# iotv2.net
KiCad netlist of a schematic drawn in Altium Designer
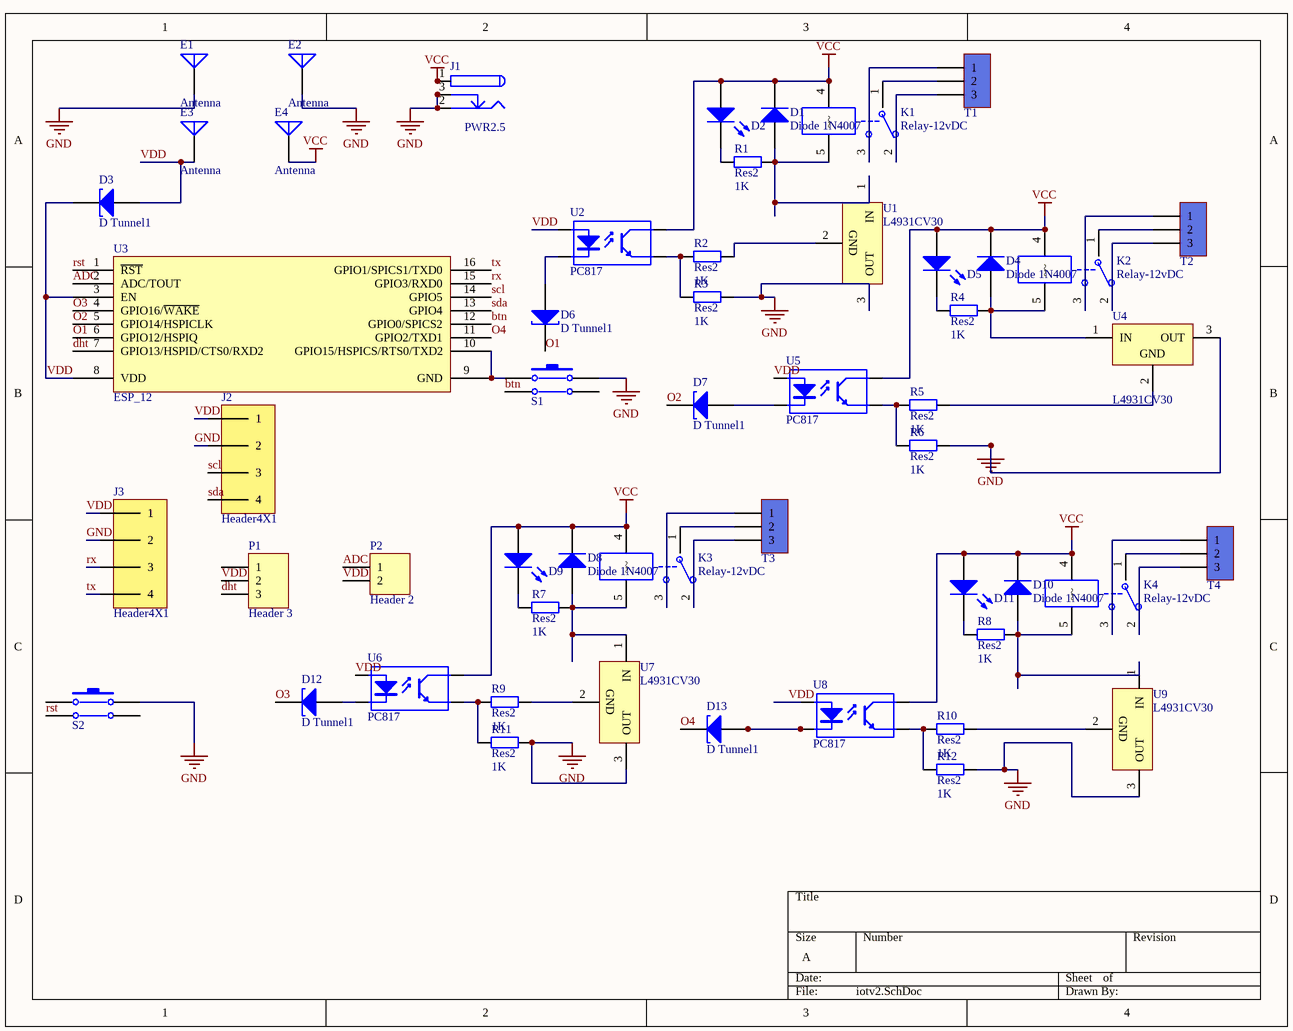
[diagram p0: iotv2.SchDoc]

(export (version "E")
  (design (tool "Eeschema 10.0.6"))
  (components
    (comp (ref "D1")
      (value "Diode 1N4007")
      (footprint "DO-41")
      (description "1 Amp General Purpose Rectifier")
      (fields (field (name "PUBLISHER") "Altium Limited"))
      (libsource (lib "Miscellaneous Devices") (part "Diode 1N4007"))
    )
    (comp (ref "D2")
      (value "LED 3mm")
      (footprint "LED-3mm")
      (description "Typical LED")
      (fields (field (name "DESIGNER") "Seyed Mohsen Ghasemian") (field (name "PUBLISHER") "www.picpars.com"))
      (libsource (lib "PicPars.com_usefully_Library") (part "LED 3mm"))
    )
    (comp (ref "D3")
      (value "D Tunnel1")
      (footprint "3.2X1.6X1.1")
      (description "Tunnel Diode - RLC Model")
      (fields (field (name "PUBLISHER") "Altium Limited"))
      (libsource (lib "Miscellaneous Devices") (part "D Tunnel1"))
    )
    (comp (ref "D4")
      (value "Diode 1N4007")
      (footprint "DO-41")
      (description "1 Amp General Purpose Rectifier")
      (fields (field (name "PUBLISHER") "Altium Limited"))
      (libsource (lib "Miscellaneous Devices") (part "Diode 1N4007"))
    )
    (comp (ref "D5")
      (value "LED 3mm")
      (footprint "LED-3mm")
      (description "Typical LED")
      (fields (field (name "DESIGNER") "Seyed Mohsen Ghasemian") (field (name "PUBLISHER") "www.picpars.com"))
      (libsource (lib "PicPars.com_usefully_Library") (part "LED 3mm"))
    )
    (comp (ref "D6")
      (value "D Tunnel1")
      (footprint "3.2X1.6X1.1")
      (description "Tunnel Diode - RLC Model")
      (fields (field (name "PUBLISHER") "Altium Limited"))
      (libsource (lib "Miscellaneous Devices") (part "D Tunnel1"))
    )
    (comp (ref "D7")
      (value "D Tunnel1")
      (footprint "3.2X1.6X1.1")
      (description "Tunnel Diode - RLC Model")
      (fields (field (name "PUBLISHER") "Altium Limited"))
      (libsource (lib "Miscellaneous Devices") (part "D Tunnel1"))
    )
    (comp (ref "D8")
      (value "Diode 1N4007")
      (footprint "DO-41")
      (description "1 Amp General Purpose Rectifier")
      (fields (field (name "PUBLISHER") "Altium Limited"))
      (libsource (lib "Miscellaneous Devices") (part "Diode 1N4007"))
    )
    (comp (ref "D9")
      (value "LED 3mm")
      (footprint "LED-3mm")
      (description "Typical LED")
      (fields (field (name "DESIGNER") "Seyed Mohsen Ghasemian") (field (name "PUBLISHER") "www.picpars.com"))
      (libsource (lib "PicPars.com_usefully_Library") (part "LED 3mm"))
    )
    (comp (ref "D10")
      (value "Diode 1N4007")
      (footprint "DO-41")
      (description "1 Amp General Purpose Rectifier")
      (fields (field (name "PUBLISHER") "Altium Limited"))
      (libsource (lib "Miscellaneous Devices") (part "Diode 1N4007"))
    )
    (comp (ref "D11")
      (value "LED 3mm")
      (footprint "LED-3mm")
      (description "Typical LED")
      (fields (field (name "DESIGNER") "Seyed Mohsen Ghasemian") (field (name "PUBLISHER") "www.picpars.com"))
      (libsource (lib "PicPars.com_usefully_Library") (part "LED 3mm"))
    )
    (comp (ref "D12")
      (value "D Tunnel1")
      (footprint "3.2X1.6X1.1")
      (description "Tunnel Diode - RLC Model")
      (fields (field (name "PUBLISHER") "Altium Limited"))
      (libsource (lib "Miscellaneous Devices") (part "D Tunnel1"))
    )
    (comp (ref "D13")
      (value "D Tunnel1")
      (footprint "3.2X1.6X1.1")
      (description "Tunnel Diode - RLC Model")
      (fields (field (name "PUBLISHER") "Altium Limited"))
      (libsource (lib "Miscellaneous Devices") (part "D Tunnel1"))
    )
    (comp (ref "E1")
      (value "Antenna")
      (footprint "PIN1")
      (description "Generic Antenna")
      (fields (field (name "PUBLISHER") "Altium Limited"))
      (libsource (lib "Miscellaneous Devices") (part "Antenna"))
    )
    (comp (ref "E2")
      (value "Antenna")
      (footprint "PIN1")
      (description "Generic Antenna")
      (fields (field (name "PUBLISHER") "Altium Limited"))
      (libsource (lib "Miscellaneous Devices") (part "Antenna"))
    )
    (comp (ref "E3")
      (value "Antenna")
      (footprint "PIN1")
      (description "Generic Antenna")
      (fields (field (name "PUBLISHER") "Altium Limited"))
      (libsource (lib "Miscellaneous Devices") (part "Antenna"))
    )
    (comp (ref "E4")
      (value "Antenna")
      (footprint "PIN1")
      (description "Generic Antenna")
      (fields (field (name "PUBLISHER") "Altium Limited"))
      (libsource (lib "Miscellaneous Devices") (part "Antenna"))
    )
    (comp (ref "J1")
      (value "PWR2.5")
      (footprint "KLD-0202")
      (description "Low Voltage Power Supply Connector")
      (fields (field (name "PUBLISHER") "Altium Limited"))
      (libsource (lib "Miscellaneous Connectors") (part "PWR2.5"))
    )
    (comp (ref "J2")
      (value "Header4X1")
      (footprint "HEADER 4X1")
      (libsource (lib "AltiumLib1") (part "Header4X1"))
    )
    (comp (ref "J3")
      (value "Header4X1")
      (footprint "HEADER 4X1")
      (libsource (lib "AltiumLib1") (part "Header4X1"))
    )
    (comp (ref "K1")
      (value "Relay-12vDC")
      (footprint "Relays")
      (description "Relay-05vDC-240AC 5A")
      (fields (field (name "DESIGNER") "Seyed Mohsen Ghasemain"))
      (libsource (lib "PicPars.com_usefully_Library") (part "Relay-05vDC"))
    )
    (comp (ref "K2")
      (value "Relay-12vDC")
      (footprint "Relays")
      (description "Relay-05vDC-240AC 5A")
      (fields (field (name "DESIGNER") "Seyed Mohsen Ghasemain"))
      (libsource (lib "PicPars.com_usefully_Library") (part "Relay-05vDC"))
    )
    (comp (ref "K3")
      (value "Relay-12vDC")
      (footprint "Relays")
      (description "Relay-05vDC-240AC 5A")
      (fields (field (name "DESIGNER") "Seyed Mohsen Ghasemain"))
      (libsource (lib "PicPars.com_usefully_Library") (part "Relay-05vDC"))
    )
    (comp (ref "K4")
      (value "Relay-12vDC")
      (footprint "Relays")
      (description "Relay-05vDC-240AC 5A")
      (fields (field (name "DESIGNER") "Seyed Mohsen Ghasemain"))
      (libsource (lib "PicPars.com_usefully_Library") (part "Relay-05vDC"))
    )
    (comp (ref "P1")
      (value "Header 3")
      (footprint "HDR1X3")
      (description "Header, 3-Pin")
      (fields (field (name "PUBLISHER") "Altium Limited"))
      (libsource (lib "Miscellaneous Connectors") (part "Header 3"))
    )
    (comp (ref "P2")
      (value "Header 2")
      (footprint "HDR1X2")
      (description "Header, 2-Pin")
      (fields (field (name "PUBLISHER") "Altium Limited"))
      (libsource (lib "Miscellaneous Connectors") (part "Header 2"))
    )
    (comp (ref "R1")
      (value "Res2")
      (footprint "AXIAL-0.4")
      (description "Resistor")
      (fields (field (name "ALTIUM_VALUE") "1K") (field (name "PUBLISHER") "Altium Limited"))
      (libsource (lib "Miscellaneous Devices") (part "Res2"))
    )
    (comp (ref "R2")
      (value "Res2")
      (footprint "AXIAL-0.4")
      (description "Resistor")
      (fields (field (name "ALTIUM_VALUE") "1K") (field (name "PUBLISHER") "Altium Limited"))
      (libsource (lib "Miscellaneous Devices") (part "Res2"))
    )
    (comp (ref "R3")
      (value "Res2")
      (footprint "AXIAL-0.4")
      (description "Resistor")
      (fields (field (name "ALTIUM_VALUE") "1K") (field (name "PUBLISHER") "Altium Limited"))
      (libsource (lib "Miscellaneous Devices") (part "Res2"))
    )
    (comp (ref "R4")
      (value "Res2")
      (footprint "AXIAL-0.4")
      (description "Resistor")
      (fields (field (name "ALTIUM_VALUE") "1K") (field (name "PUBLISHER") "Altium Limited"))
      (libsource (lib "Miscellaneous Devices") (part "Res2"))
    )
    (comp (ref "R5")
      (value "Res2")
      (footprint "AXIAL-0.4")
      (description "Resistor")
      (fields (field (name "ALTIUM_VALUE") "1K") (field (name "PUBLISHER") "Altium Limited"))
      (libsource (lib "Miscellaneous Devices") (part "Res2"))
    )
    (comp (ref "R6")
      (value "Res2")
      (footprint "AXIAL-0.4")
      (description "Resistor")
      (fields (field (name "ALTIUM_VALUE") "1K") (field (name "PUBLISHER") "Altium Limited"))
      (libsource (lib "Miscellaneous Devices") (part "Res2"))
    )
    (comp (ref "R7")
      (value "Res2")
      (footprint "AXIAL-0.4")
      (description "Resistor")
      (fields (field (name "ALTIUM_VALUE") "1K") (field (name "PUBLISHER") "Altium Limited"))
      (libsource (lib "Miscellaneous Devices") (part "Res2"))
    )
    (comp (ref "R8")
      (value "Res2")
      (footprint "AXIAL-0.4")
      (description "Resistor")
      (fields (field (name "ALTIUM_VALUE") "1K") (field (name "PUBLISHER") "Altium Limited"))
      (libsource (lib "Miscellaneous Devices") (part "Res2"))
    )
    (comp (ref "R9")
      (value "Res2")
      (footprint "AXIAL-0.4")
      (description "Resistor")
      (fields (field (name "ALTIUM_VALUE") "1K") (field (name "PUBLISHER") "Altium Limited"))
      (libsource (lib "Miscellaneous Devices") (part "Res2"))
    )
    (comp (ref "R10")
      (value "Res2")
      (footprint "AXIAL-0.4")
      (description "Resistor")
      (fields (field (name "ALTIUM_VALUE") "1K") (field (name "PUBLISHER") "Altium Limited"))
      (libsource (lib "Miscellaneous Devices") (part "Res2"))
    )
    (comp (ref "R11")
      (value "Res2")
      (footprint "AXIAL-0.4")
      (description "Resistor")
      (fields (field (name "ALTIUM_VALUE") "1K") (field (name "PUBLISHER") "Altium Limited"))
      (libsource (lib "Miscellaneous Devices") (part "Res2"))
    )
    (comp (ref "R12")
      (value "Res2")
      (footprint "AXIAL-0.4")
      (description "Resistor")
      (fields (field (name "ALTIUM_VALUE") "1K") (field (name "PUBLISHER") "Altium Limited"))
      (libsource (lib "Miscellaneous Devices") (part "Res2"))
    )
    (comp (ref "S1")
      (value "PUSH BUTTON DOUBLE")
      (footprint "PUSH BUTTON")
      (description "Switch")
      (libsource (lib "AltiumLib1") (part "PUSH BUTTON DOUBLE"))
    )
    (comp (ref "S2")
      (value "PUSH BUTTON DOUBLE")
      (footprint "PUSH BUTTON")
      (description "Switch")
      (libsource (lib "AltiumLib1") (part "PUSH BUTTON DOUBLE"))
    )
    (comp (ref "T1")
      (value "Terminal")
      (footprint "Terminal 1*3")
      (description "Terminal 3 Pin 250VAC 16A")
      (fields (field (name "DESIGNER") "Seyed Mohsen Ghasemain") (field (name "E-MAIL") "picpars@gmail.com"))
      (libsource (lib "PicPars.com_usefully_Library") (part "Terminal 1*3"))
    )
    (comp (ref "T2")
      (value "Terminal")
      (footprint "Terminal 1*3")
      (description "Terminal 3 Pin 250VAC 16A")
      (fields (field (name "DESIGNER") "Seyed Mohsen Ghasemain") (field (name "E-MAIL") "picpars@gmail.com"))
      (libsource (lib "PicPars.com_usefully_Library") (part "Terminal 1*3"))
    )
    (comp (ref "T3")
      (value "Terminal")
      (footprint "Terminal 1*3")
      (description "Terminal 3 Pin 250VAC 16A")
      (fields (field (name "DESIGNER") "Seyed Mohsen Ghasemain") (field (name "E-MAIL") "picpars@gmail.com"))
      (libsource (lib "PicPars.com_usefully_Library") (part "Terminal 1*3"))
    )
    (comp (ref "T4")
      (value "Terminal")
      (footprint "Terminal 1*3")
      (description "Terminal 3 Pin 250VAC 16A")
      (fields (field (name "DESIGNER") "Seyed Mohsen Ghasemain") (field (name "E-MAIL") "picpars@gmail.com"))
      (libsource (lib "PicPars.com_usefully_Library") (part "Terminal 1*3"))
    )
    (comp (ref "U1")
      (value "L4931CV30")
      (footprint "TO-220A")
      (description "250mA, Very Low Drop ( 0.4V) Voltage Regulator")
      (fields (field (name "PUBLISHER") "Altium Limited"))
      (libsource (lib "") (part "L4931CV30_1"))
    )
    (comp (ref "U2")
      (value "PC817")
      (footprint "DIP4")
      (description "4-Pin Phototransistor Optocoupler")
      (libsource (lib "AltiumLib1") (part "OPTCOUPLER_01"))
    )
    (comp (ref "U3")
      (value "ESP_12")
      (footprint "ESP_12")
      (description "ESP-12 Wi-Fi Module by AI-Thinker")
      (libsource (lib "ESP8266") (part "ESP_12"))
    )
    (comp (ref "U4")
      (value "L4931CV30")
      (footprint "TO-220A")
      (description "250mA, Very Low Drop ( 0.4V) Voltage Regulator")
      (fields (field (name "PUBLISHER") "Altium Limited"))
      (libsource (lib "ST Power Mgt Voltage Regulator") (part "L4931CV30"))
    )
    (comp (ref "U5")
      (value "PC817")
      (footprint "DIP4")
      (description "4-Pin Phototransistor Optocoupler")
      (libsource (lib "AltiumLib1") (part "OPTCOUPLER_01"))
    )
    (comp (ref "U6")
      (value "PC817")
      (footprint "DIP4")
      (description "4-Pin Phototransistor Optocoupler")
      (libsource (lib "AltiumLib1") (part "OPTCOUPLER_01"))
    )
    (comp (ref "U7")
      (value "L4931CV30")
      (footprint "TO-220A")
      (description "250mA, Very Low Drop ( 0.4V) Voltage Regulator")
      (fields (field (name "PUBLISHER") "Altium Limited"))
      (libsource (lib "") (part "L4931CV30_1"))
    )
    (comp (ref "U8")
      (value "PC817")
      (footprint "DIP4")
      (description "4-Pin Phototransistor Optocoupler")
      (libsource (lib "AltiumLib1") (part "OPTCOUPLER_01"))
    )
    (comp (ref "U9")
      (value "L4931CV30")
      (footprint "TO-220A")
      (description "250mA, Very Low Drop ( 0.4V) Voltage Regulator")
      (fields (field (name "PUBLISHER") "Altium Limited"))
      (libsource (lib "") (part "L4931CV30_1"))
    )
  )
  (nets
    (net (code "1") (name "/ADC") (class "Default")
      (node (ref "P2") (pin "1") (pinfunction "1_1") (pintype "passive"))
      (node (ref "U3") (pin "2") (pinfunction "ADC/TOUT_2") (pintype "passive"))
    )
    (net (code "2") (name "/O1") (class "Default")
      (node (ref "D6") (pin "2") (pinfunction "K_2") (pintype "passive"))
      (node (ref "U3") (pin "6") (pinfunction "GPIO12/HSPIQ_6") (pintype "passive"))
    )
    (net (code "3") (name "/O2") (class "Default")
      (node (ref "D7") (pin "2") (pinfunction "K_2") (pintype "passive"))
      (node (ref "U3") (pin "5") (pinfunction "GPIO14/HSPICLK_5") (pintype "passive"))
    )
    (net (code "4") (name "/O3") (class "Default")
      (node (ref "D12") (pin "2") (pinfunction "K_2") (pintype "passive"))
      (node (ref "U3") (pin "4") (pinfunction "GPIO16/~{WAKE}_4") (pintype "passive"))
    )
    (net (code "5") (name "/O4") (class "Default")
      (node (ref "D13") (pin "2") (pinfunction "K_2") (pintype "passive"))
      (node (ref "U3") (pin "11") (pinfunction "GPIO2/TXD1_11") (pintype "passive"))
    )
    (net (code "6") (name "/VDD") (class "Default")
      (node (ref "D3") (pin "1") (pinfunction "A_1") (pintype "passive"))
      (node (ref "D3") (pin "2") (pinfunction "K_2") (pintype "passive"))
      (node (ref "E3") (pin "1") (pinfunction "A_1") (pintype "passive"))
      (node (ref "J2") (pin "1") (pinfunction "1_1") (pintype "passive"))
      (node (ref "J3") (pin "1") (pinfunction "1_1") (pintype "passive"))
      (node (ref "P1") (pin "2") (pinfunction "2_2") (pintype "passive"))
      (node (ref "P2") (pin "2") (pinfunction "2_2") (pintype "passive"))
      (node (ref "U2") (pin "1") (pinfunction "A_1") (pintype "passive"))
      (node (ref "U3") (pin "3") (pinfunction "EN_3") (pintype "passive"))
      (node (ref "U3") (pin "8") (pinfunction "VDD_8") (pintype "passive"))
      (node (ref "U5") (pin "1") (pinfunction "A_1") (pintype "passive"))
      (node (ref "U6") (pin "1") (pinfunction "A_1") (pintype "passive"))
      (node (ref "U8") (pin "1") (pinfunction "A_1") (pintype "passive"))
    )
    (net (code "7") (name "/btn") (class "Default")
      (node (ref "S1") (pin "3") (pinfunction "3_3") (pintype "passive"))
      (node (ref "U3") (pin "12") (pinfunction "GPIO0/SPICS2_12") (pintype "passive"))
    )
    (net (code "8") (name "/dht") (class "Default")
      (node (ref "P1") (pin "3") (pinfunction "3_3") (pintype "passive"))
      (node (ref "U3") (pin "7") (pinfunction "GPIO13/HSPID/CTS0/RXD2_7") (pintype "passive"))
    )
    (net (code "9") (name "/rst") (class "Default")
      (node (ref "S2") (pin "3") (pinfunction "3_3") (pintype "passive"))
      (node (ref "U3") (pin "1") (pinfunction "~{RST}_1") (pintype "passive"))
    )
    (net (code "10") (name "/rx") (class "Default")
      (node (ref "J3") (pin "3") (pinfunction "3_3") (pintype "passive"))
      (node (ref "U3") (pin "15") (pinfunction "GPIO3/RXD0_15") (pintype "passive"))
    )
    (net (code "11") (name "/scl") (class "Default")
      (node (ref "J2") (pin "3") (pinfunction "3_3") (pintype "passive"))
      (node (ref "U3") (pin "14") (pinfunction "GPIO5_14") (pintype "passive"))
    )
    (net (code "12") (name "/sda") (class "Default")
      (node (ref "J2") (pin "4") (pinfunction "4_4") (pintype "passive"))
      (node (ref "U3") (pin "13") (pinfunction "GPIO4_13") (pintype "passive"))
    )
    (net (code "13") (name "/tx") (class "Default")
      (node (ref "J3") (pin "4") (pinfunction "4_4") (pintype "passive"))
      (node (ref "U3") (pin "16") (pinfunction "GPIO1/SPICS1/TXD0_16") (pintype "passive"))
    )
    (net (code "14") (name "GND") (class "Default")
      (node (ref "E1") (pin "1") (pinfunction "A_1") (pintype "passive"))
      (node (ref "E2") (pin "1") (pinfunction "A_1") (pintype "passive"))
      (node (ref "J1") (pin "2") (pinfunction "2_2") (pintype "power_in"))
      (node (ref "J1") (pin "2A") (pinfunction "2A_2A") (pintype "power_in"))
      (node (ref "J1") (pin "2B") (pinfunction "2B_2B") (pintype "power_in"))
      (node (ref "J1") (pin "3") (pinfunction "3_3") (pintype "power_in"))
      (node (ref "J1") (pin "3A") (pinfunction "3A_3A") (pintype "power_in"))
      (node (ref "J1") (pin "3B") (pinfunction "3B_3B") (pintype "power_in"))
      (node (ref "J2") (pin "2") (pinfunction "2_2") (pintype "passive"))
      (node (ref "J3") (pin "2") (pinfunction "2_2") (pintype "passive"))
      (node (ref "R11") (pin "2") (pinfunction "2_2") (pintype "passive"))
      (node (ref "R12") (pin "2") (pinfunction "2_2") (pintype "passive"))
      (node (ref "R3") (pin "2") (pinfunction "2_2") (pintype "passive"))
      (node (ref "R6") (pin "2") (pinfunction "2_2") (pintype "passive"))
      (node (ref "S1") (pin "2") (pinfunction "2_2") (pintype "passive"))
      (node (ref "S2") (pin "2") (pinfunction "2_2") (pintype "passive"))
      (node (ref "U1") (pin "3") (pinfunction "OUT_3") (pintype "power_in"))
      (node (ref "U4") (pin "3") (pinfunction "OUT_3") (pintype "power_in"))
      (node (ref "U7") (pin "3") (pinfunction "OUT_3") (pintype "power_in"))
      (node (ref "U9") (pin "3") (pinfunction "OUT_3") (pintype "power_in"))
    )
    (net (code "15") (name "Net-(D1-A)") (class "Default")
      (node (ref "D1") (pin "1") (pinfunction "A_1") (pintype "passive"))
      (node (ref "K1") (pin "5") (pinfunction "~_5") (pintype "passive"))
      (node (ref "R1") (pin "2") (pinfunction "2_2") (pintype "passive"))
      (node (ref "U1") (pin "1") (pinfunction "IN_1") (pintype "power_in"))
    )
    (net (code "16") (name "Net-(D2-K)") (class "Default")
      (node (ref "D2") (pin "2") (pinfunction "K_2") (pintype "passive"))
      (node (ref "R1") (pin "1") (pinfunction "1_1") (pintype "passive"))
    )
    (net (code "17") (name "Net-(D4-A)") (class "Default")
      (node (ref "D4") (pin "1") (pinfunction "A_1") (pintype "passive"))
      (node (ref "K2") (pin "5") (pinfunction "~_5") (pintype "passive"))
      (node (ref "R4") (pin "2") (pinfunction "2_2") (pintype "passive"))
      (node (ref "U4") (pin "1") (pinfunction "IN_1") (pintype "power_in"))
    )
    (net (code "18") (name "Net-(D5-K)") (class "Default")
      (node (ref "D5") (pin "2") (pinfunction "K_2") (pintype "passive"))
      (node (ref "R4") (pin "1") (pinfunction "1_1") (pintype "passive"))
    )
    (net (code "19") (name "Net-(D6-A)") (class "Default")
      (node (ref "D6") (pin "1") (pinfunction "A_1") (pintype "passive"))
      (node (ref "U2") (pin "2") (pinfunction "K_2") (pintype "passive"))
    )
    (net (code "20") (name "Net-(D7-A)") (class "Default")
      (node (ref "D7") (pin "1") (pinfunction "A_1") (pintype "passive"))
      (node (ref "U5") (pin "2") (pinfunction "K_2") (pintype "passive"))
    )
    (net (code "21") (name "Net-(D8-A)") (class "Default")
      (node (ref "D8") (pin "1") (pinfunction "A_1") (pintype "passive"))
      (node (ref "K3") (pin "5") (pinfunction "~_5") (pintype "passive"))
      (node (ref "R7") (pin "2") (pinfunction "2_2") (pintype "passive"))
      (node (ref "U7") (pin "1") (pinfunction "IN_1") (pintype "power_in"))
    )
    (net (code "22") (name "Net-(D9-K)") (class "Default")
      (node (ref "D9") (pin "2") (pinfunction "K_2") (pintype "passive"))
      (node (ref "R7") (pin "1") (pinfunction "1_1") (pintype "passive"))
    )
    (net (code "23") (name "Net-(D10-A)") (class "Default")
      (node (ref "D10") (pin "1") (pinfunction "A_1") (pintype "passive"))
      (node (ref "K4") (pin "5") (pinfunction "~_5") (pintype "passive"))
      (node (ref "R8") (pin "2") (pinfunction "2_2") (pintype "passive"))
      (node (ref "U9") (pin "1") (pinfunction "IN_1") (pintype "power_in"))
    )
    (net (code "24") (name "Net-(D11-K)") (class "Default")
      (node (ref "D11") (pin "2") (pinfunction "K_2") (pintype "passive"))
      (node (ref "R8") (pin "1") (pinfunction "1_1") (pintype "passive"))
    )
    (net (code "25") (name "Net-(D12-A)") (class "Default")
      (node (ref "D12") (pin "1") (pinfunction "A_1") (pintype "passive"))
      (node (ref "U6") (pin "2") (pinfunction "K_2") (pintype "passive"))
    )
    (net (code "26") (name "Net-(D13-A)") (class "Default")
      (node (ref "D13") (pin "1") (pinfunction "A_1") (pintype "passive"))
      (node (ref "U8") (pin "2") (pinfunction "K_2") (pintype "passive"))
    )
    (net (code "27") (name "Net-(K1-COM)") (class "Default")
      (node (ref "K1") (pin "1") (pinfunction "COM_1") (pintype "passive"))
      (node (ref "T1") (pin "2") (pinfunction "2_2") (pintype "passive"))
    )
    (net (code "28") (name "Net-(K1-NC)") (class "Default")
      (node (ref "K1") (pin "2") (pinfunction "NC_2") (pintype "passive"))
      (node (ref "T1") (pin "3") (pinfunction "3_3") (pintype "passive"))
    )
    (net (code "29") (name "Net-(K1-NO)") (class "Default")
      (node (ref "K1") (pin "3") (pinfunction "NO_3") (pintype "passive"))
      (node (ref "T1") (pin "1") (pinfunction "1_1") (pintype "passive"))
    )
    (net (code "30") (name "Net-(K2-COM)") (class "Default")
      (node (ref "K2") (pin "1") (pinfunction "COM_1") (pintype "passive"))
      (node (ref "T2") (pin "2") (pinfunction "2_2") (pintype "passive"))
    )
    (net (code "31") (name "Net-(K2-NC)") (class "Default")
      (node (ref "K2") (pin "2") (pinfunction "NC_2") (pintype "passive"))
      (node (ref "T2") (pin "3") (pinfunction "3_3") (pintype "passive"))
    )
    (net (code "32") (name "Net-(K2-NO)") (class "Default")
      (node (ref "K2") (pin "3") (pinfunction "NO_3") (pintype "passive"))
      (node (ref "T2") (pin "1") (pinfunction "1_1") (pintype "passive"))
    )
    (net (code "33") (name "Net-(K3-COM)") (class "Default")
      (node (ref "K3") (pin "1") (pinfunction "COM_1") (pintype "passive"))
      (node (ref "T3") (pin "2") (pinfunction "2_2") (pintype "passive"))
    )
    (net (code "34") (name "Net-(K3-NC)") (class "Default")
      (node (ref "K3") (pin "2") (pinfunction "NC_2") (pintype "passive"))
      (node (ref "T3") (pin "3") (pinfunction "3_3") (pintype "passive"))
    )
    (net (code "35") (name "Net-(K3-NO)") (class "Default")
      (node (ref "K3") (pin "3") (pinfunction "NO_3") (pintype "passive"))
      (node (ref "T3") (pin "1") (pinfunction "1_1") (pintype "passive"))
    )
    (net (code "36") (name "Net-(K4-COM)") (class "Default")
      (node (ref "K4") (pin "1") (pinfunction "COM_1") (pintype "passive"))
      (node (ref "T4") (pin "2") (pinfunction "2_2") (pintype "passive"))
    )
    (net (code "37") (name "Net-(K4-NC)") (class "Default")
      (node (ref "K4") (pin "2") (pinfunction "NC_2") (pintype "passive"))
      (node (ref "T4") (pin "3") (pinfunction "3_3") (pintype "passive"))
    )
    (net (code "38") (name "Net-(K4-NO)") (class "Default")
      (node (ref "K4") (pin "3") (pinfunction "NO_3") (pintype "passive"))
      (node (ref "T4") (pin "1") (pinfunction "1_1") (pintype "passive"))
    )
    (net (code "39") (name "Net-(U1-GND)") (class "Default")
      (node (ref "R2") (pin "2") (pinfunction "2_2") (pintype "passive"))
      (node (ref "U1") (pin "2") (pinfunction "GND_2") (pintype "power_in"))
    )
    (net (code "40") (name "Net-(U2-E)") (class "Default")
      (node (ref "R2") (pin "1") (pinfunction "1_1") (pintype "passive"))
      (node (ref "R3") (pin "1") (pinfunction "1_1") (pintype "passive"))
      (node (ref "U2") (pin "3") (pinfunction "E_3") (pintype "passive"))
    )
    (net (code "41") (name "Net-(U3-GND)") (class "Default")
      (node (ref "S1") (pin "1") (pinfunction "1_1") (pintype "passive"))
      (node (ref "U3") (pin "10") (pinfunction "GPIO15/HSPICS/RTS0/TXD2_10") (pintype "passive"))
      (node (ref "U3") (pin "9") (pinfunction "GND_9") (pintype "passive"))
    )
    (net (code "42") (name "Net-(U4-GND)") (class "Default")
      (node (ref "R5") (pin "2") (pinfunction "2_2") (pintype "passive"))
      (node (ref "U4") (pin "2") (pinfunction "GND_2") (pintype "power_in"))
    )
    (net (code "43") (name "Net-(U5-E)") (class "Default")
      (node (ref "R5") (pin "1") (pinfunction "1_1") (pintype "passive"))
      (node (ref "R6") (pin "1") (pinfunction "1_1") (pintype "passive"))
      (node (ref "U5") (pin "3") (pinfunction "E_3") (pintype "passive"))
    )
    (net (code "44") (name "Net-(U6-E)") (class "Default")
      (node (ref "R11") (pin "1") (pinfunction "1_1") (pintype "passive"))
      (node (ref "R9") (pin "1") (pinfunction "1_1") (pintype "passive"))
      (node (ref "U6") (pin "3") (pinfunction "E_3") (pintype "passive"))
    )
    (net (code "45") (name "Net-(U7-GND)") (class "Default")
      (node (ref "R9") (pin "2") (pinfunction "2_2") (pintype "passive"))
      (node (ref "U7") (pin "2") (pinfunction "GND_2") (pintype "power_in"))
    )
    (net (code "46") (name "Net-(U8-E)") (class "Default")
      (node (ref "R10") (pin "1") (pinfunction "1_1") (pintype "passive"))
      (node (ref "R12") (pin "1") (pinfunction "1_1") (pintype "passive"))
      (node (ref "U8") (pin "3") (pinfunction "E_3") (pintype "passive"))
    )
    (net (code "47") (name "Net-(U9-GND)") (class "Default")
      (node (ref "R10") (pin "2") (pinfunction "2_2") (pintype "passive"))
      (node (ref "U9") (pin "2") (pinfunction "GND_2") (pintype "power_in"))
    )
    (net (code "48") (name "VCC") (class "Default")
      (node (ref "D1") (pin "2") (pinfunction "K_2") (pintype "passive"))
      (node (ref "D10") (pin "2") (pinfunction "K_2") (pintype "passive"))
      (node (ref "D11") (pin "1") (pinfunction "A_1") (pintype "passive"))
      (node (ref "D2") (pin "1") (pinfunction "A_1") (pintype "passive"))
      (node (ref "D4") (pin "2") (pinfunction "K_2") (pintype "passive"))
      (node (ref "D5") (pin "1") (pinfunction "A_1") (pintype "passive"))
      (node (ref "D8") (pin "2") (pinfunction "K_2") (pintype "passive"))
      (node (ref "D9") (pin "1") (pinfunction "A_1") (pintype "passive"))
      (node (ref "E4") (pin "1") (pinfunction "A_1") (pintype "passive"))
      (node (ref "J1") (pin "1") (pinfunction "1_1") (pintype "power_in"))
      (node (ref "J1") (pin "1A") (pinfunction "1A_1A") (pintype "power_in"))
      (node (ref "J1") (pin "1B") (pinfunction "1B_1B") (pintype "power_in"))
      (node (ref "K1") (pin "4") (pinfunction "~_4") (pintype "passive"))
      (node (ref "K2") (pin "4") (pinfunction "~_4") (pintype "passive"))
      (node (ref "K3") (pin "4") (pinfunction "~_4") (pintype "passive"))
      (node (ref "K4") (pin "4") (pinfunction "~_4") (pintype "passive"))
      (node (ref "U2") (pin "4") (pinfunction "C_4") (pintype "passive"))
      (node (ref "U5") (pin "4") (pinfunction "C_4") (pintype "passive"))
      (node (ref "U6") (pin "4") (pinfunction "C_4") (pintype "passive"))
      (node (ref "U8") (pin "4") (pinfunction "C_4") (pintype "passive"))
    )
    (net (code "49") (name "unconnected-(P1-Pad1)") (class "Default")
      (node (ref "P1") (pin "1") (pinfunction "1_1") (pintype "passive"))
    )
    (net (code "50") (name "unconnected-(S1-Pad4)") (class "Default")
      (node (ref "S1") (pin "4") (pinfunction "4_4") (pintype "passive"))
    )
    (net (code "51") (name "unconnected-(S2-Pad1)") (class "Default")
      (node (ref "S2") (pin "1") (pinfunction "1_1") (pintype "passive"))
    )
    (net (code "52") (name "unconnected-(S2-Pad4)") (class "Default")
      (node (ref "S2") (pin "4") (pinfunction "4_4") (pintype "passive"))
    )
  )
)
